# do_an_2.net
KiCad netlist of a schematic drawn in EAGLE
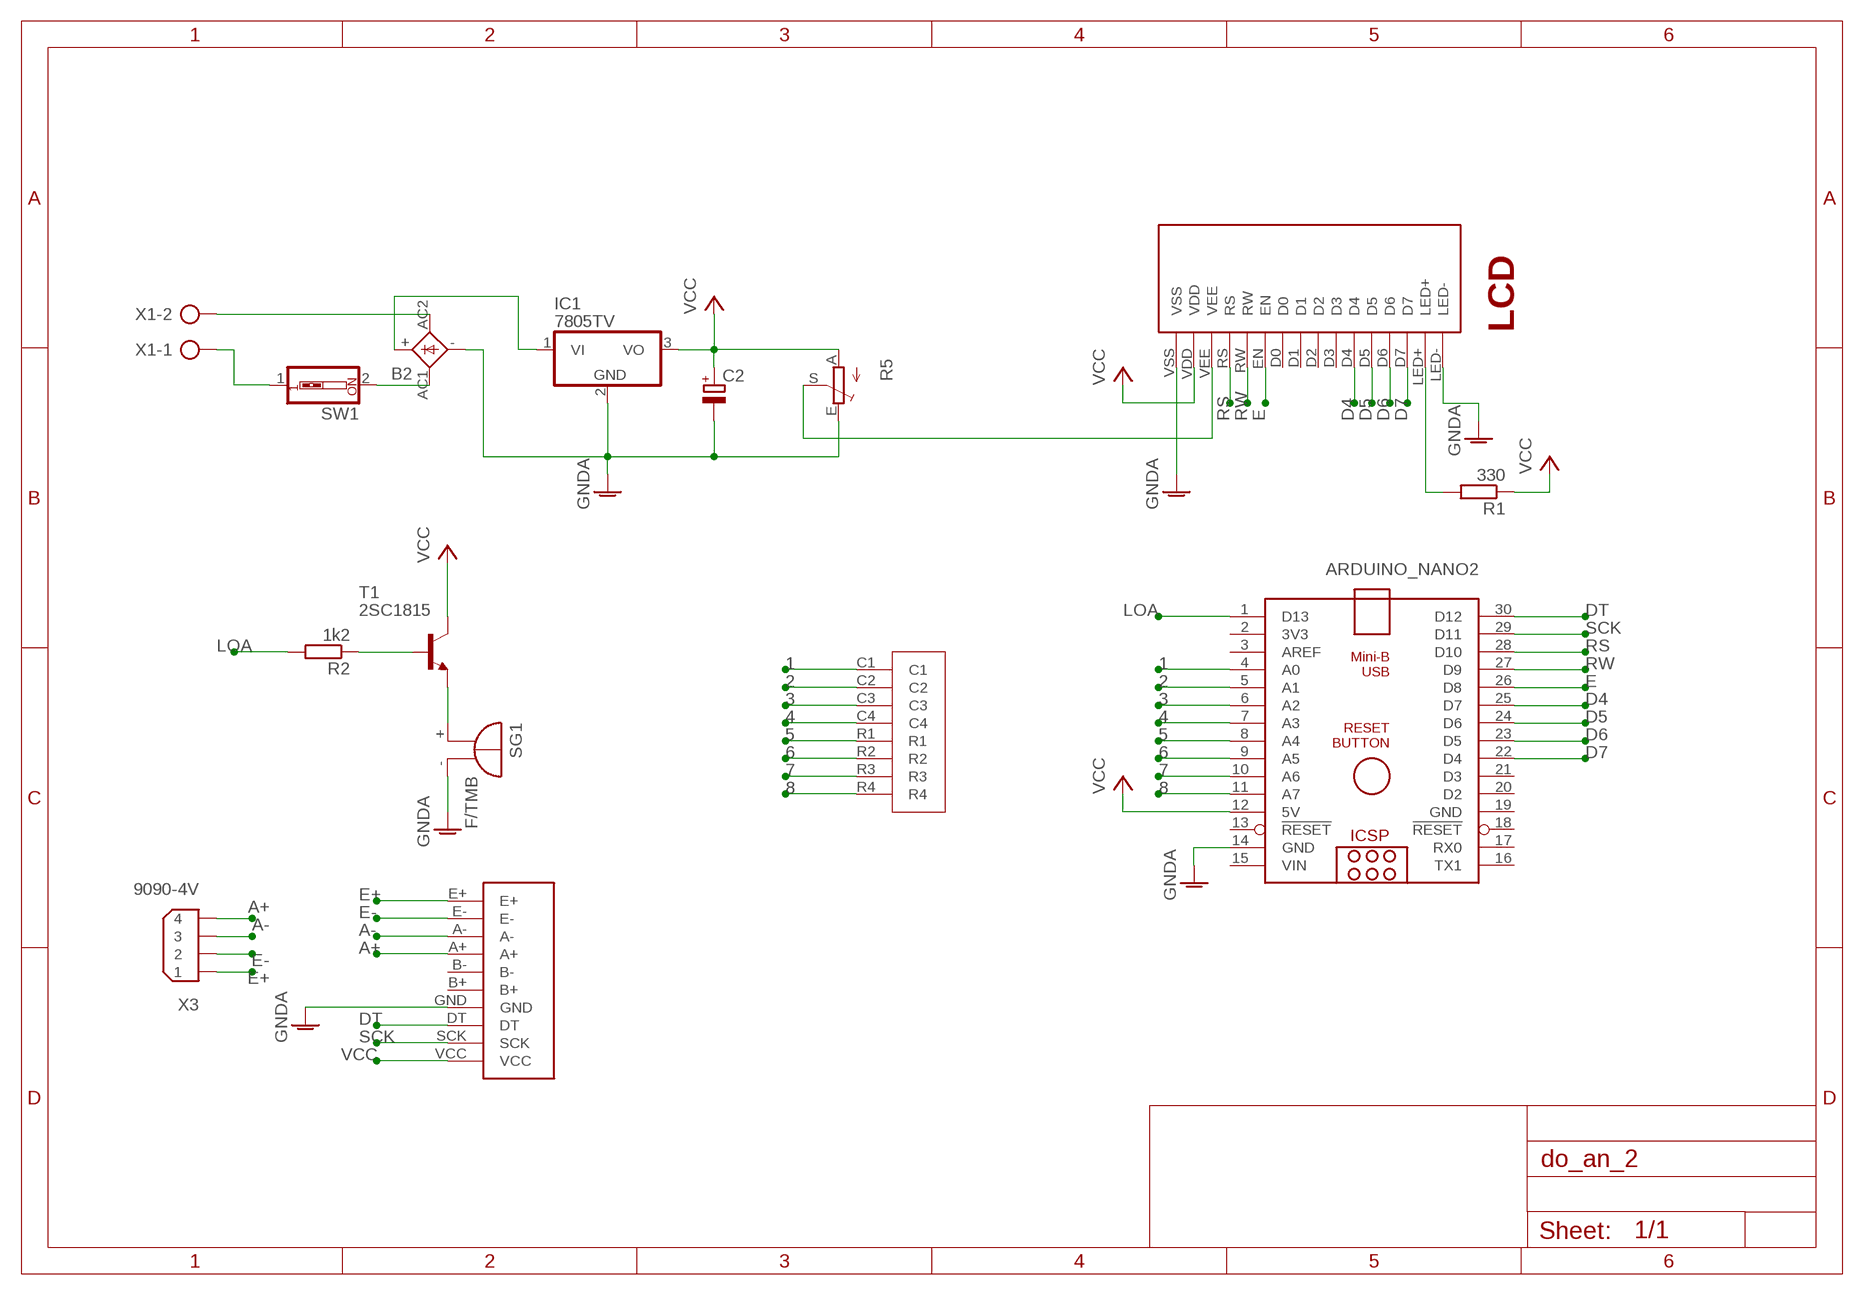
[diagram p0: schematic, sheet 1]

(export (version "E")
  (design (tool "Eeschema 10.0.6"))
  (components
    (comp (ref "ARDUINO_NANO2")
      (value "ARDUINO_NANO")
      (footprint "eagle-import:ARDUINO_NANO")
      (libsource (lib "eagle-import") (part "ARDUINO_NANO"))
    )
    (comp (ref "B2")
      (value "2KBP")
      (footprint "eagle-import:2KBP")
      (libsource (lib "eagle-import") (part "2KBP"))
    )
    (comp (ref "C2")
      (value "CPOL-EUE5-10.5")
      (footprint "eagle-import:E5-10,5")
      (libsource (lib "eagle-import") (part "CPOL-EUE5-10.5"))
    )
    (comp (ref "IC1")
      (value "7805TV")
      (footprint "eagle-import:TO220V")
      (libsource (lib "eagle-import") (part "78TV05"))
    )
    (comp (ref "R1")
      (value "330")
      (footprint "eagle-import:0207_10")
      (libsource (lib "eagle-import") (part "R-EU_0207/10"))
    )
    (comp (ref "R2")
      (value "1k2")
      (footprint "eagle-import:0207_10")
      (libsource (lib "eagle-import") (part "R-EU_0207/10"))
    )
    (comp (ref "R5")
      (value "TRIM_EU-S64W")
      (footprint "eagle-import:S64W")
      (libsource (lib "eagle-import") (part "TRIM_EU-S64W"))
    )
    (comp (ref "SG1")
      (value "F/TMB")
      (footprint "eagle-import:F_TMB")
      (libsource (lib "eagle-import") (part "F/TMB"))
    )
    (comp (ref "SW1")
      (value "SW_DIP-1")
      (footprint "eagle-import:EDG-01")
      (libsource (lib "eagle-import") (part "SW_DIP-1"))
    )
    (comp (ref "T1")
      (value "2SC1815")
      (footprint "eagle-import:TO92-ECB")
      (libsource (lib "eagle-import") (part "2SC1815"))
    )
    (comp (ref "U$1")
      (value "LCD20X4")
      (footprint "eagle-import:LCD20X4")
      (libsource (lib "eagle-import") (part "LCD20X4"))
    )
    (comp (ref "U$2")
      (value "MA_TRAN_PHIM")
      (footprint "eagle-import:MA_TRAN_PHIM")
      (libsource (lib "eagle-import") (part "MA_TRAN_PHIM"))
    )
    (comp (ref "U$3")
      (value "MACHMAUXANH")
      (footprint "eagle-import:MACHMAUXANH")
      (libsource (lib "eagle-import") (part "MACHMAUXANH"))
    )
    (comp (ref "X1")
      (value "AK300/2")
      (footprint "eagle-import:AK300_2")
      (libsource (lib "eagle-import") (part "AK300/2"))
    )
    (comp (ref "X3")
      (value "9090-4V")
      (footprint "eagle-import:9090-4V")
      (libsource (lib "eagle-import") (part "9090-4V"))
    )
  )
  (nets
    (net (code "1") (name "/1") (class "Default")
      (node (ref "ARDUINO_NANO2") (pin "4") (pinfunction "A0_4") (pintype "bidirectional"))
      (node (ref "U$2") (pin "C1") (pinfunction "C1_C1") (pintype "bidirectional"))
    )
    (net (code "2") (name "/2") (class "Default")
      (node (ref "ARDUINO_NANO2") (pin "5") (pinfunction "A1_5") (pintype "bidirectional"))
      (node (ref "U$2") (pin "C2") (pinfunction "C2_C2") (pintype "bidirectional"))
    )
    (net (code "3") (name "/3") (class "Default")
      (node (ref "ARDUINO_NANO2") (pin "6") (pinfunction "A2_6") (pintype "bidirectional"))
      (node (ref "U$2") (pin "C3") (pinfunction "C3_C3") (pintype "bidirectional"))
    )
    (net (code "4") (name "/4") (class "Default")
      (node (ref "ARDUINO_NANO2") (pin "7") (pinfunction "A3_7") (pintype "bidirectional"))
      (node (ref "U$2") (pin "C4") (pinfunction "C4_C4") (pintype "bidirectional"))
    )
    (net (code "5") (name "/5") (class "Default")
      (node (ref "ARDUINO_NANO2") (pin "8") (pinfunction "A4_8") (pintype "bidirectional"))
      (node (ref "U$2") (pin "R1") (pinfunction "R1_R1") (pintype "bidirectional"))
    )
    (net (code "6") (name "/6") (class "Default")
      (node (ref "ARDUINO_NANO2") (pin "9") (pinfunction "A5_9") (pintype "bidirectional"))
      (node (ref "U$2") (pin "R2") (pinfunction "R2_R2") (pintype "bidirectional"))
    )
    (net (code "7") (name "/7") (class "Default")
      (node (ref "ARDUINO_NANO2") (pin "10") (pinfunction "A6_10") (pintype "bidirectional"))
      (node (ref "U$2") (pin "R3") (pinfunction "R3_R3") (pintype "bidirectional"))
    )
    (net (code "8") (name "/8") (class "Default")
      (node (ref "ARDUINO_NANO2") (pin "11") (pinfunction "A7_11") (pintype "bidirectional"))
      (node (ref "U$2") (pin "R4") (pinfunction "R4_R4") (pintype "bidirectional"))
    )
    (net (code "9") (name "/A+") (class "Default")
      (node (ref "U$3") (pin "A+") (pinfunction "A+_A+") (pintype "bidirectional"))
      (node (ref "X3") (pin "4") (pinfunction "4_4") (pintype "passive"))
    )
    (net (code "10") (name "/A-") (class "Default")
      (node (ref "U$3") (pin "A-") (pinfunction "A-_A-") (pintype "bidirectional"))
      (node (ref "X3") (pin "3") (pinfunction "3_3") (pintype "passive"))
    )
    (net (code "11") (name "/D4") (class "Default")
      (node (ref "ARDUINO_NANO2") (pin "25") (pinfunction "D7_25") (pintype "bidirectional"))
      (node (ref "U$1") (pin "D4") (pinfunction "D4_D4") (pintype "bidirectional"))
    )
    (net (code "12") (name "/D5") (class "Default")
      (node (ref "ARDUINO_NANO2") (pin "24") (pinfunction "D6_24") (pintype "bidirectional"))
      (node (ref "U$1") (pin "D5") (pinfunction "D5_D5") (pintype "bidirectional"))
    )
    (net (code "13") (name "/D6") (class "Default")
      (node (ref "ARDUINO_NANO2") (pin "23") (pinfunction "D5_23") (pintype "bidirectional"))
      (node (ref "U$1") (pin "D6") (pinfunction "D6_D6") (pintype "bidirectional"))
    )
    (net (code "14") (name "/D7") (class "Default")
      (node (ref "ARDUINO_NANO2") (pin "22") (pinfunction "D4_22") (pintype "bidirectional"))
      (node (ref "U$1") (pin "D7") (pinfunction "D7_D7") (pintype "bidirectional"))
    )
    (net (code "15") (name "/DT") (class "Default")
      (node (ref "ARDUINO_NANO2") (pin "30") (pinfunction "D12_30") (pintype "bidirectional"))
      (node (ref "U$3") (pin "DT") (pinfunction "DT_DT") (pintype "bidirectional"))
    )
    (net (code "16") (name "/E") (class "Default")
      (node (ref "ARDUINO_NANO2") (pin "26") (pinfunction "D8_26") (pintype "bidirectional"))
      (node (ref "U$1") (pin "EN") (pinfunction "EN_EN") (pintype "bidirectional"))
    )
    (net (code "17") (name "/E+") (class "Default")
      (node (ref "U$3") (pin "E+") (pinfunction "E+_E+") (pintype "bidirectional"))
      (node (ref "X3") (pin "1") (pinfunction "1_1") (pintype "passive"))
    )
    (net (code "18") (name "/E-") (class "Default")
      (node (ref "U$3") (pin "E-") (pinfunction "E-_E-") (pintype "bidirectional"))
      (node (ref "X3") (pin "2") (pinfunction "2_2") (pintype "passive"))
    )
    (net (code "19") (name "/GND") (class "Default")
      (node (ref "ARDUINO_NANO2") (pin "19") (pinfunction "GND_19") (pintype "power_in"))
    )
    (net (code "20") (name "/LOA") (class "Default")
      (node (ref "ARDUINO_NANO2") (pin "1") (pinfunction "D13_1") (pintype "bidirectional"))
      (node (ref "R2") (pin "2") (pinfunction "2_2") (pintype "passive"))
    )
    (net (code "21") (name "/RS") (class "Default")
      (node (ref "ARDUINO_NANO2") (pin "28") (pinfunction "D10_28") (pintype "bidirectional"))
      (node (ref "U$1") (pin "RS") (pinfunction "RS_RS") (pintype "bidirectional"))
    )
    (net (code "22") (name "/RW") (class "Default")
      (node (ref "ARDUINO_NANO2") (pin "27") (pinfunction "D9_27") (pintype "bidirectional"))
      (node (ref "U$1") (pin "RW") (pinfunction "RW_RW") (pintype "bidirectional"))
    )
    (net (code "23") (name "/SCK") (class "Default")
      (node (ref "ARDUINO_NANO2") (pin "29") (pinfunction "D11_29") (pintype "bidirectional"))
      (node (ref "U$3") (pin "SCK") (pinfunction "SCK_SCK") (pintype "bidirectional"))
    )
    (net (code "24") (name "/VIN") (class "Default")
      (node (ref "ARDUINO_NANO2") (pin "15") (pinfunction "VIN_15") (pintype "power_in"))
    )
    (net (code "25") (name "GNDA") (class "Default")
      (node (ref "ARDUINO_NANO2") (pin "14") (pinfunction "GND_14") (pintype "power_in"))
      (node (ref "B2") (pin "-") (pinfunction "-_-") (pintype "passive"))
      (node (ref "C2") (pin "-") (pinfunction "-_-") (pintype "passive"))
      (node (ref "IC1") (pin "2") (pinfunction "GND_2") (pintype "passive"))
      (node (ref "R5") (pin "E") (pinfunction "E_E") (pintype "passive"))
      (node (ref "SG1") (pin "-") (pinfunction "-_-") (pintype "passive"))
      (node (ref "U$1") (pin "LED-") (pinfunction "LED-_LED-") (pintype "bidirectional"))
      (node (ref "U$1") (pin "VSS") (pinfunction "VSS_VSS") (pintype "bidirectional"))
      (node (ref "U$3") (pin "GND") (pinfunction "GND_GND") (pintype "bidirectional"))
    )
    (net (code "26") (name "Net-(B2-PadAC1)") (class "Default")
      (node (ref "B2") (pin "AC1") (pinfunction "AC1_AC1") (pintype "passive"))
      (node (ref "SW1") (pin "2") (pinfunction "2_2") (pintype "passive"))
    )
    (net (code "27") (name "Net-(IC1-VI)") (class "Default")
      (node (ref "B2") (pin "+") (pinfunction "+_+") (pintype "passive"))
      (node (ref "IC1") (pin "1") (pinfunction "VI_1") (pintype "input"))
    )
    (net (code "28") (name "Net-(R1-Pad2)") (class "Default")
      (node (ref "R1") (pin "2") (pinfunction "2_2") (pintype "passive"))
      (node (ref "U$1") (pin "LED+") (pinfunction "LED+_LED+") (pintype "bidirectional"))
    )
    (net (code "29") (name "Net-(R2-Pad1)") (class "Default")
      (node (ref "R2") (pin "1") (pinfunction "1_1") (pintype "passive"))
      (node (ref "T1") (pin "B") (pinfunction "B_B") (pintype "passive"))
    )
    (net (code "30") (name "Net-(R5-PadS)") (class "Default")
      (node (ref "R5") (pin "S") (pinfunction "S_S") (pintype "passive"))
      (node (ref "U$1") (pin "VEE") (pinfunction "VEE_VEE") (pintype "bidirectional"))
    )
    (net (code "31") (name "Net-(SG1-Pad+)") (class "Default")
      (node (ref "SG1") (pin "+") (pinfunction "+_+") (pintype "passive"))
      (node (ref "T1") (pin "E") (pinfunction "E_E") (pintype "passive"))
    )
    (net (code "32") (name "Net-(X1A-KL)") (class "Default")
      (node (ref "SW1") (pin "1") (pinfunction "1_1") (pintype "passive"))
      (node (ref "X1") (pin "1") (pinfunction "KL_1") (pintype "passive"))
    )
    (net (code "33") (name "Net-(X1B-KL)") (class "Default")
      (node (ref "B2") (pin "AC2") (pinfunction "AC2_AC2") (pintype "passive"))
      (node (ref "X1") (pin "2") (pinfunction "KL_2") (pintype "passive"))
    )
    (net (code "34") (name "VCC") (class "Default")
      (node (ref "ARDUINO_NANO2") (pin "12") (pinfunction "5V_12") (pintype "power_in"))
      (node (ref "C2") (pin "+") (pinfunction "+_+") (pintype "passive"))
      (node (ref "IC1") (pin "3") (pinfunction "VO_3") (pintype "passive"))
      (node (ref "R1") (pin "1") (pinfunction "1_1") (pintype "passive"))
      (node (ref "R5") (pin "A") (pinfunction "A_A") (pintype "passive"))
      (node (ref "T1") (pin "C") (pinfunction "C_C") (pintype "passive"))
      (node (ref "U$1") (pin "VDD") (pinfunction "VDD_VDD") (pintype "bidirectional"))
      (node (ref "U$3") (pin "VCC") (pinfunction "VCC_VCC") (pintype "bidirectional"))
    )
    (net (code "35") (name "unconnected-(ARDUINO_NANO2-3V3-Pad2)") (class "Default")
      (node (ref "ARDUINO_NANO2") (pin "2") (pinfunction "3V3_2") (pintype "output"))
    )
    (net (code "36") (name "unconnected-(ARDUINO_NANO2-AREF-Pad3)") (class "Default")
      (node (ref "ARDUINO_NANO2") (pin "3") (pinfunction "AREF_3") (pintype "input"))
    )
    (net (code "37") (name "unconnected-(ARDUINO_NANO2-D2-Pad20)") (class "Default")
      (node (ref "ARDUINO_NANO2") (pin "20") (pinfunction "D2_20") (pintype "bidirectional"))
    )
    (net (code "38") (name "unconnected-(ARDUINO_NANO2-D3-Pad21)") (class "Default")
      (node (ref "ARDUINO_NANO2") (pin "21") (pinfunction "D3_21") (pintype "bidirectional"))
    )
    (net (code "39") (name "unconnected-(ARDUINO_NANO2-RX0-Pad17)") (class "Default")
      (node (ref "ARDUINO_NANO2") (pin "17") (pinfunction "RX0_17") (pintype "bidirectional"))
    )
    (net (code "40") (name "unconnected-(ARDUINO_NANO2-TX1-Pad16)") (class "Default")
      (node (ref "ARDUINO_NANO2") (pin "16") (pinfunction "TX1_16") (pintype "bidirectional"))
    )
    (net (code "41") (name "unconnected-(ARDUINO_NANO2-~{RESET}-Pad13)") (class "Default")
      (node (ref "ARDUINO_NANO2") (pin "13") (pinfunction "~{RESET}_13") (pintype "input"))
    )
    (net (code "42") (name "unconnected-(ARDUINO_NANO2-~{RESET}-Pad18)") (class "Default")
      (node (ref "ARDUINO_NANO2") (pin "18") (pinfunction "~{RESET}_18") (pintype "input"))
    )
    (net (code "43") (name "unconnected-(U$1-PadD0)") (class "Default")
      (node (ref "U$1") (pin "D0") (pinfunction "D0_D0") (pintype "bidirectional"))
    )
    (net (code "44") (name "unconnected-(U$1-PadD1)") (class "Default")
      (node (ref "U$1") (pin "D1") (pinfunction "D1_D1") (pintype "bidirectional"))
    )
    (net (code "45") (name "unconnected-(U$1-PadD2)") (class "Default")
      (node (ref "U$1") (pin "D2") (pinfunction "D2_D2") (pintype "bidirectional"))
    )
    (net (code "46") (name "unconnected-(U$1-PadD3)") (class "Default")
      (node (ref "U$1") (pin "D3") (pinfunction "D3_D3") (pintype "bidirectional"))
    )
    (net (code "47") (name "unconnected-(U$3-PadB+)") (class "Default")
      (node (ref "U$3") (pin "B+") (pinfunction "B+_B+") (pintype "bidirectional"))
    )
    (net (code "48") (name "unconnected-(U$3-PadB-)") (class "Default")
      (node (ref "U$3") (pin "B-") (pinfunction "B-_B-") (pintype "bidirectional"))
    )
  )
)
